# RPU_BUS.net
KiCad netlist of a schematic drawn in EAGLE
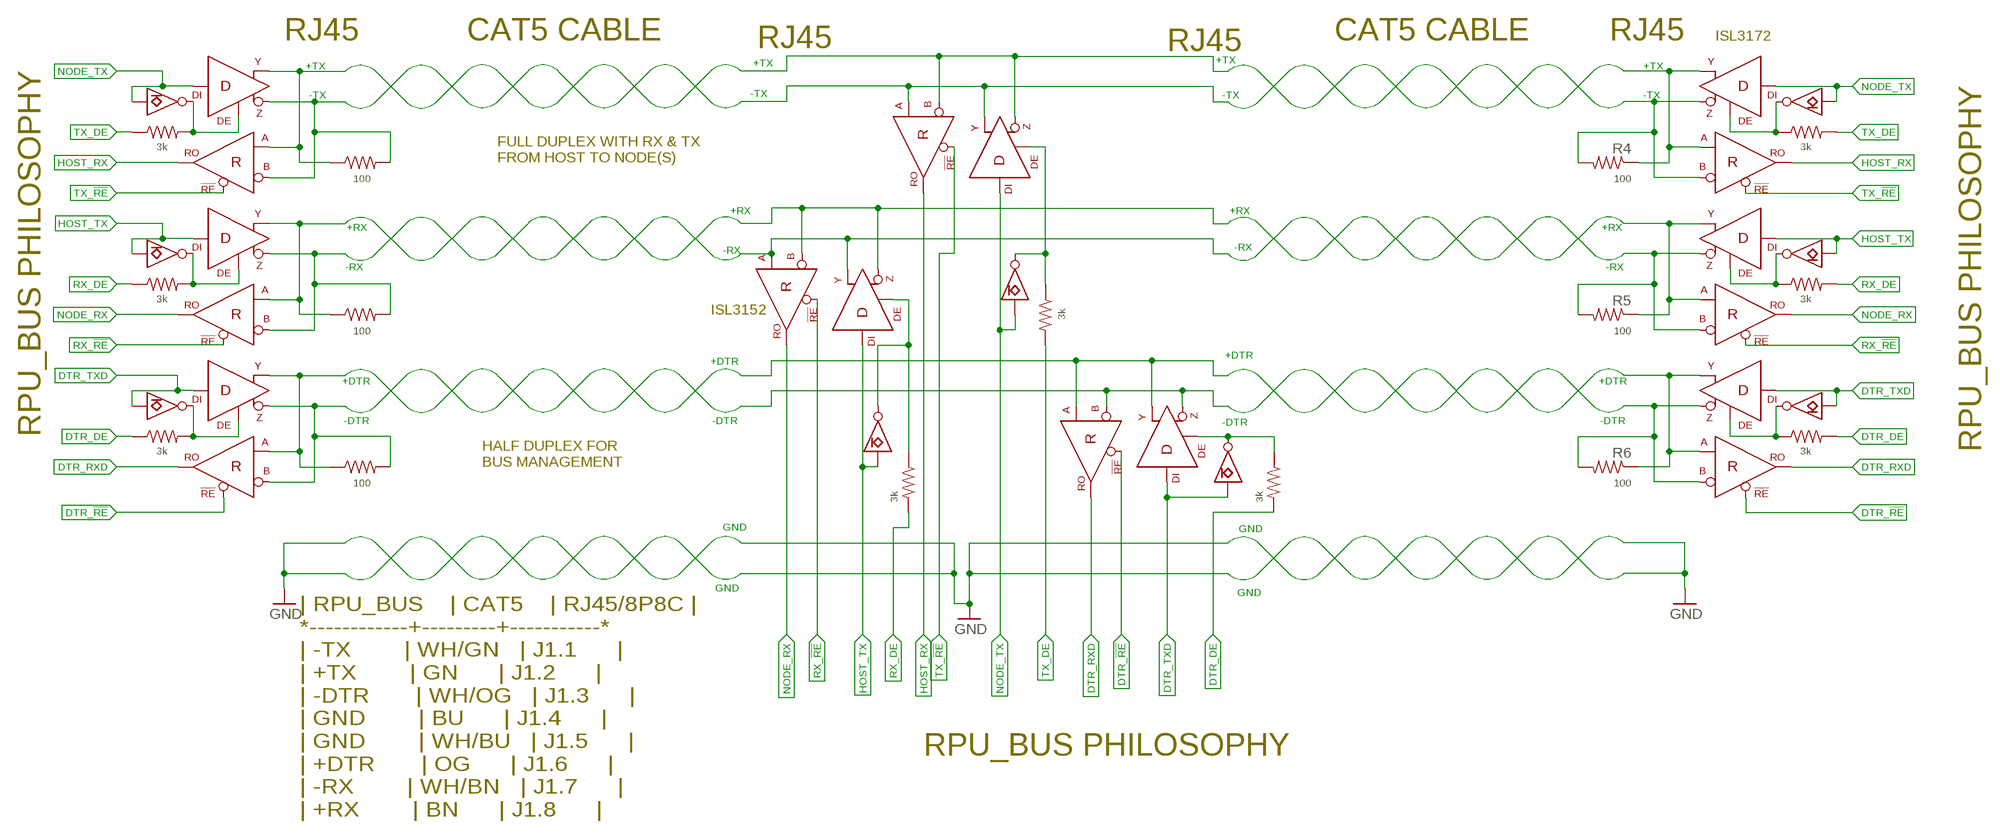
[diagram p0: schematic, sheet 1]

(export (version "E")
  (design (tool "Eeschema 10.0.6"))
  (components
    (comp (ref "R1")
      (value "100")
      (footprint "eagle-import:C1206(3216)")
      (libsource (lib "eagle-import") (part "R1206"))
    )
    (comp (ref "R2")
      (value "100")
      (footprint "eagle-import:C1206(3216)")
      (libsource (lib "eagle-import") (part "R1206"))
    )
    (comp (ref "R3")
      (value "100")
      (footprint "eagle-import:C1206(3216)")
      (libsource (lib "eagle-import") (part "R1206"))
    )
    (comp (ref "R4")
      (value "100")
      (footprint "eagle-import:C1206(3216)")
      (libsource (lib "eagle-import") (part "R1206"))
    )
    (comp (ref "R5")
      (value "100")
      (footprint "eagle-import:C1206(3216)")
      (libsource (lib "eagle-import") (part "R1206"))
    )
    (comp (ref "R6")
      (value "100")
      (footprint "eagle-import:C1206(3216)")
      (libsource (lib "eagle-import") (part "R1206"))
    )
    (comp (ref "R7")
      (value "3k")
      (footprint "eagle-import:C1206(3216)")
      (libsource (lib "eagle-import") (part "R1206"))
    )
    (comp (ref "R8")
      (value "3k")
      (footprint "eagle-import:C1206(3216)")
      (libsource (lib "eagle-import") (part "R1206"))
    )
    (comp (ref "R9")
      (value "3k")
      (footprint "eagle-import:C1206(3216)")
      (libsource (lib "eagle-import") (part "R1206"))
    )
    (comp (ref "R10")
      (value "3k")
      (footprint "eagle-import:C1206(3216)")
      (libsource (lib "eagle-import") (part "R1206"))
    )
    (comp (ref "R11")
      (value "3k")
      (footprint "eagle-import:C1206(3216)")
      (libsource (lib "eagle-import") (part "R1206"))
    )
    (comp (ref "R12")
      (value "3k")
      (footprint "eagle-import:C1206(3216)")
      (libsource (lib "eagle-import") (part "R1206"))
    )
    (comp (ref "R13")
      (value "3k")
      (footprint "eagle-import:C1206(3216)")
      (libsource (lib "eagle-import") (part "R1206"))
    )
    (comp (ref "R14")
      (value "3k")
      (footprint "eagle-import:C1206(3216)")
      (libsource (lib "eagle-import") (part "R1206"))
    )
    (comp (ref "R15")
      (value "3k")
      (footprint "eagle-import:C1206(3216)")
      (libsource (lib "eagle-import") (part "R1206"))
    )
    (comp (ref "U$1")
      (value "DIFF_D")
      (footprint "eagle-import:NA-10")
      (libsource (lib "eagle-import") (part "DIFF_D"))
    )
    (comp (ref "U$2")
      (value "DIFF_D")
      (footprint "eagle-import:NA-10")
      (libsource (lib "eagle-import") (part "DIFF_D"))
    )
    (comp (ref "U$3")
      (value "DIFF_D")
      (footprint "eagle-import:NA-10")
      (libsource (lib "eagle-import") (part "DIFF_D"))
    )
    (comp (ref "U$4")
      (value "DIFF_D")
      (footprint "eagle-import:NA-10")
      (libsource (lib "eagle-import") (part "DIFF_D"))
    )
    (comp (ref "U$5")
      (value "DIFF_D")
      (footprint "eagle-import:NA-10")
      (libsource (lib "eagle-import") (part "DIFF_D"))
    )
    (comp (ref "U$6")
      (value "DIFF_D")
      (footprint "eagle-import:NA-10")
      (libsource (lib "eagle-import") (part "DIFF_D"))
    )
    (comp (ref "U$7")
      (value "DIFF_D")
      (footprint "eagle-import:NA-10")
      (libsource (lib "eagle-import") (part "DIFF_D"))
    )
    (comp (ref "U$8")
      (value "DIFF_D")
      (footprint "eagle-import:NA-10")
      (libsource (lib "eagle-import") (part "DIFF_D"))
    )
    (comp (ref "U$9")
      (value "DIFF_D")
      (footprint "eagle-import:NA-10")
      (libsource (lib "eagle-import") (part "DIFF_D"))
    )
    (comp (ref "U$10")
      (value "INVERT-OC")
      (footprint "eagle-import:NA-20")
      (libsource (lib "eagle-import") (part "INVERT-OC"))
    )
    (comp (ref "U$11")
      (value "INVERT-OC")
      (footprint "eagle-import:NA-20")
      (libsource (lib "eagle-import") (part "INVERT-OC"))
    )
    (comp (ref "U$12")
      (value "INVERT-OC")
      (footprint "eagle-import:NA-20")
      (libsource (lib "eagle-import") (part "INVERT-OC"))
    )
    (comp (ref "U$13")
      (value "INVERT-OC")
      (footprint "eagle-import:NA-20")
      (libsource (lib "eagle-import") (part "INVERT-OC"))
    )
    (comp (ref "U$14")
      (value "INVERT-OC")
      (footprint "eagle-import:NA-20")
      (libsource (lib "eagle-import") (part "INVERT-OC"))
    )
    (comp (ref "U$15")
      (value "INVERT-OC")
      (footprint "eagle-import:NA-20")
      (libsource (lib "eagle-import") (part "INVERT-OC"))
    )
    (comp (ref "U$16")
      (value "INVERT-OC")
      (footprint "eagle-import:NA-20")
      (libsource (lib "eagle-import") (part "INVERT-OC"))
    )
    (comp (ref "U$17")
      (value "INVERT-OC")
      (footprint "eagle-import:NA-20")
      (libsource (lib "eagle-import") (part "INVERT-OC"))
    )
    (comp (ref "U$18")
      (value "INVERT-OC")
      (footprint "eagle-import:NA-20")
      (libsource (lib "eagle-import") (part "INVERT-OC"))
    )
    (comp (ref "U1")
      (value "DIFF_R")
      (footprint "eagle-import:NA-10")
      (libsource (lib "eagle-import") (part "DIFF_R"))
    )
    (comp (ref "U2")
      (value "DIFF_R")
      (footprint "eagle-import:NA-10")
      (libsource (lib "eagle-import") (part "DIFF_R"))
    )
    (comp (ref "U3")
      (value "DIFF_R")
      (footprint "eagle-import:NA-10")
      (libsource (lib "eagle-import") (part "DIFF_R"))
    )
    (comp (ref "U4")
      (value "DIFF_R")
      (footprint "eagle-import:NA-10")
      (libsource (lib "eagle-import") (part "DIFF_R"))
    )
    (comp (ref "U5")
      (value "DIFF_R")
      (footprint "eagle-import:NA-10")
      (libsource (lib "eagle-import") (part "DIFF_R"))
    )
    (comp (ref "U6")
      (value "DIFF_R")
      (footprint "eagle-import:NA-10")
      (libsource (lib "eagle-import") (part "DIFF_R"))
    )
    (comp (ref "U7")
      (value "DIFF_R")
      (footprint "eagle-import:NA-10")
      (libsource (lib "eagle-import") (part "DIFF_R"))
    )
    (comp (ref "U8")
      (value "DIFF_R")
      (footprint "eagle-import:NA-10")
      (libsource (lib "eagle-import") (part "DIFF_R"))
    )
    (comp (ref "U9")
      (value "DIFF_R")
      (footprint "eagle-import:NA-10")
      (libsource (lib "eagle-import") (part "DIFF_R"))
    )
  )
  (nets
    (net (code "1") (name "/+DTR") (class "Default")
      (node (ref "R3") (pin "1") (pinfunction "1_1") (pintype "passive"))
      (node (ref "R6") (pin "1") (pinfunction "1_1") (pintype "passive"))
      (node (ref "U$4") (pin "3") (pinfunction "Y_3") (pintype "bidirectional"))
      (node (ref "U$5") (pin "3") (pinfunction "Y_3") (pintype "bidirectional"))
      (node (ref "U$6") (pin "3") (pinfunction "Y_3") (pintype "bidirectional"))
      (node (ref "U2") (pin "1") (pinfunction "A_1") (pintype "bidirectional"))
      (node (ref "U4") (pin "1") (pinfunction "A_1") (pintype "bidirectional"))
      (node (ref "U5") (pin "1") (pinfunction "A_1") (pintype "bidirectional"))
    )
    (net (code "2") (name "/+RX") (class "Default")
      (node (ref "R2") (pin "1") (pinfunction "1_1") (pintype "passive"))
      (node (ref "R5") (pin "1") (pinfunction "1_1") (pintype "passive"))
      (node (ref "U$2") (pin "4") (pinfunction "Z_4") (pintype "bidirectional"))
      (node (ref "U$7") (pin "3") (pinfunction "Y_3") (pintype "bidirectional"))
      (node (ref "U$9") (pin "3") (pinfunction "Y_3") (pintype "bidirectional"))
      (node (ref "U1") (pin "1") (pinfunction "A_1") (pintype "bidirectional"))
      (node (ref "U6") (pin "1") (pinfunction "A_1") (pintype "bidirectional"))
      (node (ref "U8") (pin "4") (pinfunction "B_4") (pintype "bidirectional"))
    )
    (net (code "3") (name "/+TX") (class "Default")
      (node (ref "R1") (pin "1") (pinfunction "1_1") (pintype "passive"))
      (node (ref "R4") (pin "1") (pinfunction "1_1") (pintype "passive"))
      (node (ref "U$1") (pin "3") (pinfunction "Y_3") (pintype "bidirectional"))
      (node (ref "U$3") (pin "3") (pinfunction "Y_3") (pintype "bidirectional"))
      (node (ref "U$8") (pin "4") (pinfunction "Z_4") (pintype "bidirectional"))
      (node (ref "U3") (pin "4") (pinfunction "B_4") (pintype "bidirectional"))
      (node (ref "U7") (pin "1") (pinfunction "A_1") (pintype "bidirectional"))
      (node (ref "U9") (pin "1") (pinfunction "A_1") (pintype "bidirectional"))
    )
    (net (code "4") (name "/-DTR") (class "Default")
      (node (ref "R3") (pin "2") (pinfunction "2_2") (pintype "passive"))
      (node (ref "R6") (pin "2") (pinfunction "2_2") (pintype "passive"))
      (node (ref "U$4") (pin "4") (pinfunction "Z_4") (pintype "bidirectional"))
      (node (ref "U$5") (pin "4") (pinfunction "Z_4") (pintype "bidirectional"))
      (node (ref "U$6") (pin "4") (pinfunction "Z_4") (pintype "bidirectional"))
      (node (ref "U2") (pin "4") (pinfunction "B_4") (pintype "bidirectional"))
      (node (ref "U4") (pin "4") (pinfunction "B_4") (pintype "bidirectional"))
      (node (ref "U5") (pin "4") (pinfunction "B_4") (pintype "bidirectional"))
    )
    (net (code "5") (name "/-RX") (class "Default")
      (node (ref "R2") (pin "2") (pinfunction "2_2") (pintype "passive"))
      (node (ref "R5") (pin "2") (pinfunction "2_2") (pintype "passive"))
      (node (ref "U$2") (pin "3") (pinfunction "Y_3") (pintype "bidirectional"))
      (node (ref "U$7") (pin "4") (pinfunction "Z_4") (pintype "bidirectional"))
      (node (ref "U$9") (pin "4") (pinfunction "Z_4") (pintype "bidirectional"))
      (node (ref "U1") (pin "4") (pinfunction "B_4") (pintype "bidirectional"))
      (node (ref "U6") (pin "4") (pinfunction "B_4") (pintype "bidirectional"))
      (node (ref "U8") (pin "1") (pinfunction "A_1") (pintype "bidirectional"))
    )
    (net (code "6") (name "/-TX") (class "Default")
      (node (ref "R1") (pin "2") (pinfunction "2_2") (pintype "passive"))
      (node (ref "R4") (pin "2") (pinfunction "2_2") (pintype "passive"))
      (node (ref "U$1") (pin "4") (pinfunction "Z_4") (pintype "bidirectional"))
      (node (ref "U$3") (pin "4") (pinfunction "Z_4") (pintype "bidirectional"))
      (node (ref "U$8") (pin "3") (pinfunction "Y_3") (pintype "bidirectional"))
      (node (ref "U3") (pin "1") (pinfunction "A_1") (pintype "bidirectional"))
      (node (ref "U7") (pin "4") (pinfunction "B_4") (pintype "bidirectional"))
      (node (ref "U9") (pin "4") (pinfunction "B_4") (pintype "bidirectional"))
    )
    (net (code "7") (name "/DTR_~{RE}") (class "Default")
      (node (ref "U2") (pin "2") (pinfunction "~{RE}_2") (pintype "bidirectional"))
      (node (ref "U4") (pin "2") (pinfunction "~{RE}_2") (pintype "bidirectional"))
      (node (ref "U5") (pin "2") (pinfunction "~{RE}_2") (pintype "bidirectional"))
    )
    (net (code "8") (name "/RX_~{RE}") (class "Default")
      (node (ref "U1") (pin "2") (pinfunction "~{RE}_2") (pintype "bidirectional"))
      (node (ref "U6") (pin "2") (pinfunction "~{RE}_2") (pintype "bidirectional"))
      (node (ref "U8") (pin "2") (pinfunction "~{RE}_2") (pintype "bidirectional"))
    )
    (net (code "9") (name "/TX_~{RE}") (class "Default")
      (node (ref "U3") (pin "2") (pinfunction "~{RE}_2") (pintype "bidirectional"))
      (node (ref "U7") (pin "2") (pinfunction "~{RE}_2") (pintype "bidirectional"))
      (node (ref "U9") (pin "2") (pinfunction "~{RE}_2") (pintype "bidirectional"))
    )
    (net (code "10") (name "DTR_DE") (class "Default")
      (node (ref "R12") (pin "2") (pinfunction "2_2") (pintype "passive"))
      (node (ref "R15") (pin "2") (pinfunction "2_2") (pintype "passive"))
      (node (ref "R9") (pin "1") (pinfunction "1_1") (pintype "passive"))
    )
    (net (code "11") (name "DTR_RXD") (class "Default")
      (node (ref "U2") (pin "3") (pinfunction "RO_3") (pintype "bidirectional"))
      (node (ref "U4") (pin "3") (pinfunction "RO_3") (pintype "bidirectional"))
      (node (ref "U5") (pin "3") (pinfunction "RO_3") (pintype "bidirectional"))
    )
    (net (code "12") (name "DTR_TXD") (class "Default")
      (node (ref "U$14") (pin "2") (pinfunction "IN_2") (pintype "bidirectional"))
      (node (ref "U$16") (pin "2") (pinfunction "IN_2") (pintype "bidirectional"))
      (node (ref "U$18") (pin "2") (pinfunction "IN_2") (pintype "bidirectional"))
      (node (ref "U$4") (pin "2") (pinfunction "DI_2") (pintype "bidirectional"))
      (node (ref "U$5") (pin "2") (pinfunction "DI_2") (pintype "bidirectional"))
      (node (ref "U$6") (pin "2") (pinfunction "DI_2") (pintype "bidirectional"))
    )
    (net (code "14") (name "HOST_RX") (class "Default")
      (node (ref "U3") (pin "3") (pinfunction "RO_3") (pintype "bidirectional"))
      (node (ref "U7") (pin "3") (pinfunction "RO_3") (pintype "bidirectional"))
      (node (ref "U9") (pin "3") (pinfunction "RO_3") (pintype "bidirectional"))
    )
    (net (code "15") (name "HOST_TX") (class "Default")
      (node (ref "U$12") (pin "2") (pinfunction "IN_2") (pintype "bidirectional"))
      (node (ref "U$13") (pin "2") (pinfunction "IN_2") (pintype "bidirectional"))
      (node (ref "U$15") (pin "2") (pinfunction "IN_2") (pintype "bidirectional"))
      (node (ref "U$2") (pin "2") (pinfunction "DI_2") (pintype "bidirectional"))
      (node (ref "U$7") (pin "2") (pinfunction "DI_2") (pintype "bidirectional"))
      (node (ref "U$9") (pin "2") (pinfunction "DI_2") (pintype "bidirectional"))
    )
    (net (code "16") (name "NODE_RX") (class "Default")
      (node (ref "U1") (pin "3") (pinfunction "RO_3") (pintype "bidirectional"))
      (node (ref "U6") (pin "3") (pinfunction "RO_3") (pintype "bidirectional"))
      (node (ref "U8") (pin "3") (pinfunction "RO_3") (pintype "bidirectional"))
    )
    (net (code "17") (name "NODE_TX") (class "Default")
      (node (ref "U$1") (pin "2") (pinfunction "DI_2") (pintype "bidirectional"))
      (node (ref "U$10") (pin "2") (pinfunction "IN_2") (pintype "bidirectional"))
      (node (ref "U$11") (pin "2") (pinfunction "IN_2") (pintype "bidirectional"))
      (node (ref "U$17") (pin "2") (pinfunction "IN_2") (pintype "bidirectional"))
      (node (ref "U$3") (pin "2") (pinfunction "DI_2") (pintype "bidirectional"))
      (node (ref "U$8") (pin "2") (pinfunction "DI_2") (pintype "bidirectional"))
    )
    (net (code "18") (name "Net-(U$1-DE)") (class "Default")
      (node (ref "R8") (pin "2") (pinfunction "2_2") (pintype "passive"))
      (node (ref "U$1") (pin "1") (pinfunction "DE_1") (pintype "bidirectional"))
      (node (ref "U$10") (pin "1") (pinfunction "~{OUT}_1") (pintype "bidirectional"))
    )
    (net (code "19") (name "Net-(U$11-~{OUT})") (class "Default")
      (node (ref "R11") (pin "1") (pinfunction "1_1") (pintype "passive"))
      (node (ref "U$11") (pin "1") (pinfunction "~{OUT}_1") (pintype "bidirectional"))
      (node (ref "U$8") (pin "1") (pinfunction "DE_1") (pintype "bidirectional"))
    )
    (net (code "20") (name "Net-(U$12-~{OUT})") (class "Default")
      (node (ref "R14") (pin "1") (pinfunction "1_1") (pintype "passive"))
      (node (ref "U$12") (pin "1") (pinfunction "~{OUT}_1") (pintype "bidirectional"))
      (node (ref "U$9") (pin "1") (pinfunction "DE_1") (pintype "bidirectional"))
    )
    (net (code "21") (name "Net-(U$13-~{OUT})") (class "Default")
      (node (ref "R7") (pin "2") (pinfunction "2_2") (pintype "passive"))
      (node (ref "U$13") (pin "1") (pinfunction "~{OUT}_1") (pintype "bidirectional"))
      (node (ref "U$7") (pin "1") (pinfunction "DE_1") (pintype "bidirectional"))
    )
    (net (code "22") (name "Net-(U$14-~{OUT})") (class "Default")
      (node (ref "R9") (pin "2") (pinfunction "2_2") (pintype "passive"))
      (node (ref "U$14") (pin "1") (pinfunction "~{OUT}_1") (pintype "bidirectional"))
      (node (ref "U$4") (pin "1") (pinfunction "DE_1") (pintype "bidirectional"))
    )
    (net (code "23") (name "Net-(U$15-~{OUT})") (class "Default")
      (node (ref "R10") (pin "1") (pinfunction "1_1") (pintype "passive"))
      (node (ref "U$15") (pin "1") (pinfunction "~{OUT}_1") (pintype "bidirectional"))
      (node (ref "U$2") (pin "1") (pinfunction "DE_1") (pintype "bidirectional"))
    )
    (net (code "24") (name "Net-(U$16-~{OUT})") (class "Default")
      (node (ref "R12") (pin "1") (pinfunction "1_1") (pintype "passive"))
      (node (ref "U$16") (pin "1") (pinfunction "~{OUT}_1") (pintype "bidirectional"))
      (node (ref "U$5") (pin "1") (pinfunction "DE_1") (pintype "bidirectional"))
    )
    (net (code "25") (name "Net-(U$17-~{OUT})") (class "Default")
      (node (ref "R13") (pin "1") (pinfunction "1_1") (pintype "passive"))
      (node (ref "U$17") (pin "1") (pinfunction "~{OUT}_1") (pintype "bidirectional"))
      (node (ref "U$3") (pin "1") (pinfunction "DE_1") (pintype "bidirectional"))
    )
    (net (code "26") (name "Net-(U$18-~{OUT})") (class "Default")
      (node (ref "R15") (pin "1") (pinfunction "1_1") (pintype "passive"))
      (node (ref "U$18") (pin "1") (pinfunction "~{OUT}_1") (pintype "bidirectional"))
      (node (ref "U$6") (pin "1") (pinfunction "DE_1") (pintype "bidirectional"))
    )
    (net (code "27") (name "RX_DE") (class "Default")
      (node (ref "R10") (pin "2") (pinfunction "2_2") (pintype "passive"))
      (node (ref "R14") (pin "2") (pinfunction "2_2") (pintype "passive"))
      (node (ref "R7") (pin "1") (pinfunction "1_1") (pintype "passive"))
    )
    (net (code "28") (name "TX_DE") (class "Default")
      (node (ref "R11") (pin "2") (pinfunction "2_2") (pintype "passive"))
      (node (ref "R13") (pin "2") (pinfunction "2_2") (pintype "passive"))
      (node (ref "R8") (pin "1") (pinfunction "1_1") (pintype "passive"))
    )
  )
)
